# week6helloEcho.net
KiCad netlist of a schematic drawn in EAGLE
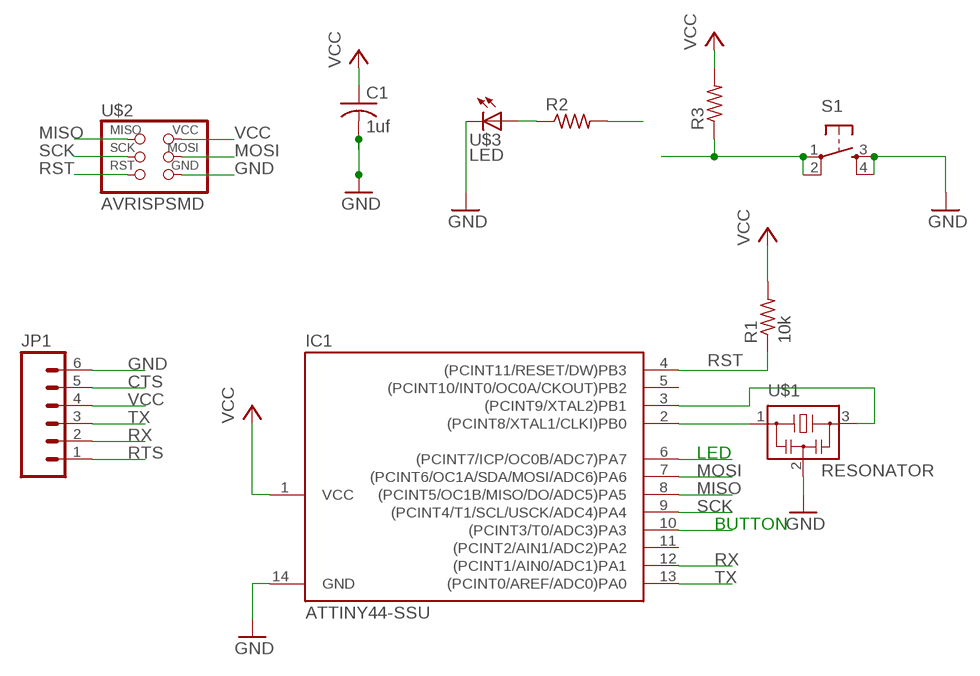
[diagram p0: schematic, sheet 1]

(export (version "E")
  (design (tool "Eeschema 10.0.6"))
  (components
    (comp (ref "C1")
      (value "1uf")
      (footprint "eagle-import:C1206")
      (libsource (lib "eagle-import") (part "C-USC1206"))
    )
    (comp (ref "IC1")
      (value "ATTINY44-SSU")
      (footprint "eagle-import:SOIC14")
      (libsource (lib "eagle-import") (part "ATTINY44-SSU"))
    )
    (comp (ref "JP1")
      (value "M06SMD")
      (footprint "eagle-import:1X06-SMD")
      (libsource (lib "eagle-import") (part "M06SMD"))
    )
    (comp (ref "R1")
      (value "10k")
      (footprint "eagle-import:R1206")
      (libsource (lib "eagle-import") (part "R-US_R1206"))
    )
    (comp (ref "R2")
      (value "RES-US1206")
      (footprint "eagle-import:R1206")
      (libsource (lib "eagle-import") (part "RES-US1206"))
    )
    (comp (ref "R3")
      (value "RES-US1206")
      (footprint "eagle-import:R1206")
      (libsource (lib "eagle-import") (part "RES-US1206"))
    )
    (comp (ref "S1")
      (value "6MM_SWITCH6MM_SWITCH")
      (footprint "eagle-import:6MM_SWITCH")
      (libsource (lib "eagle-import") (part "6MM_SWITCH6MM_SWITCH"))
    )
    (comp (ref "U$1")
      (value "RESONATOR")
      (footprint "eagle-import:EFOBM")
      (libsource (lib "eagle-import") (part "RESONATOR"))
    )
    (comp (ref "U$2")
      (value "AVRISPSMD")
      (footprint "eagle-import:2X03SMD")
      (libsource (lib "eagle-import") (part "AVRISPSMD"))
    )
    (comp (ref "U$3")
      (value "LED")
      (footprint "eagle-import:LED1206")
      (libsource (lib "eagle-import") (part "LED"))
    )
  )
  (nets
    (net (code "1") (name "/BUTTON") (class "Default")
      (node (ref "IC1") (pin "10") (pinfunction "(PCINT3/T0/ADC3)PA3_10") (pintype "bidirectional"))
      (node (ref "R3") (pin "1") (pinfunction "1_1") (pintype "passive"))
      (node (ref "S1") (pin "1") (pinfunction "P_1") (pintype "passive"))
      (node (ref "S1") (pin "2") (pinfunction "P1_2") (pintype "passive"))
    )
    (net (code "2") (name "/CTS") (class "Default")
      (node (ref "JP1") (pin "5") (pinfunction "5_5") (pintype "passive"))
    )
    (net (code "3") (name "/LED") (class "Default")
      (node (ref "IC1") (pin "6") (pinfunction "(PCINT7/ICP/OC0B/ADC7)PA7_6") (pintype "bidirectional"))
      (node (ref "R2") (pin "2") (pinfunction "2_2") (pintype "passive"))
    )
    (net (code "4") (name "/MISO") (class "Default")
      (node (ref "IC1") (pin "8") (pinfunction "(PCINT5/OC1B/MISO/DO/ADC5)PA5_8") (pintype "bidirectional"))
      (node (ref "U$2") (pin "1") (pinfunction "MISO_1") (pintype "passive"))
    )
    (net (code "5") (name "/MOSI") (class "Default")
      (node (ref "IC1") (pin "7") (pinfunction "(PCINT6/OC1A/SDA/MOSI/ADC6)PA6_7") (pintype "bidirectional"))
      (node (ref "U$2") (pin "4") (pinfunction "MOSI_4") (pintype "passive"))
    )
    (net (code "6") (name "/RST") (class "Default")
      (node (ref "IC1") (pin "4") (pinfunction "(PCINT11/RESET/DW)PB3_4") (pintype "bidirectional"))
      (node (ref "R1") (pin "1") (pinfunction "1_1") (pintype "passive"))
      (node (ref "U$2") (pin "5") (pinfunction "RST_5") (pintype "passive"))
    )
    (net (code "7") (name "/RTS") (class "Default")
      (node (ref "JP1") (pin "1") (pinfunction "1_1") (pintype "passive"))
    )
    (net (code "8") (name "/RX") (class "Default")
      (node (ref "IC1") (pin "12") (pinfunction "(PCINT1/AIN0/ADC1)PA1_12") (pintype "bidirectional"))
      (node (ref "JP1") (pin "2") (pinfunction "2_2") (pintype "passive"))
    )
    (net (code "9") (name "/SCK") (class "Default")
      (node (ref "IC1") (pin "9") (pinfunction "(PCINT4/T1/SCL/USCK/ADC4)PA4_9") (pintype "bidirectional"))
      (node (ref "U$2") (pin "3") (pinfunction "SCK_3") (pintype "passive"))
    )
    (net (code "10") (name "/TX") (class "Default")
      (node (ref "IC1") (pin "13") (pinfunction "(PCINT0/AREF/ADC0)PA0_13") (pintype "bidirectional"))
      (node (ref "JP1") (pin "3") (pinfunction "3_3") (pintype "passive"))
    )
    (net (code "11") (name "GND") (class "Default")
      (node (ref "C1") (pin "2") (pinfunction "2_2") (pintype "passive"))
      (node (ref "IC1") (pin "14") (pinfunction "GND_14") (pintype "power_in"))
      (node (ref "JP1") (pin "6") (pinfunction "6_6") (pintype "passive"))
      (node (ref "S1") (pin "3") (pinfunction "S_3") (pintype "passive"))
      (node (ref "S1") (pin "4") (pinfunction "S1_4") (pintype "passive"))
      (node (ref "U$1") (pin "2") (pinfunction "2_2") (pintype "passive"))
      (node (ref "U$2") (pin "6") (pinfunction "GND_6") (pintype "passive"))
      (node (ref "U$3") (pin "2") (pinfunction "C_2") (pintype "passive"))
    )
    (net (code "12") (name "Net-(IC1-(PCINT8{slash}XTAL1{slash}CLKI)PB0)") (class "Default")
      (node (ref "IC1") (pin "2") (pinfunction "(PCINT8/XTAL1/CLKI)PB0_2") (pintype "bidirectional"))
      (node (ref "U$1") (pin "1") (pinfunction "1_1") (pintype "passive"))
    )
    (net (code "13") (name "Net-(IC1-(PCINT9{slash}XTAL2)PB1)") (class "Default")
      (node (ref "IC1") (pin "3") (pinfunction "(PCINT9/XTAL2)PB1_3") (pintype "bidirectional"))
      (node (ref "U$1") (pin "3") (pinfunction "3_3") (pintype "passive"))
    )
    (net (code "14") (name "Net-(U$3-A)") (class "Default")
      (node (ref "R2") (pin "1") (pinfunction "1_1") (pintype "passive"))
      (node (ref "U$3") (pin "1") (pinfunction "A_1") (pintype "passive"))
    )
    (net (code "15") (name "VCC") (class "Default")
      (node (ref "C1") (pin "1") (pinfunction "1_1") (pintype "passive"))
      (node (ref "IC1") (pin "1") (pinfunction "VCC_1") (pintype "power_in"))
      (node (ref "JP1") (pin "4") (pinfunction "4_4") (pintype "passive"))
      (node (ref "R1") (pin "2") (pinfunction "2_2") (pintype "passive"))
      (node (ref "R3") (pin "2") (pinfunction "2_2") (pintype "passive"))
      (node (ref "U$2") (pin "2") (pinfunction "VCC_2") (pintype "passive"))
    )
    (net (code "16") (name "unconnected-(IC1-(PCINT2{slash}AIN1{slash}ADC2)PA2-Pad11)") (class "Default")
      (node (ref "IC1") (pin "11") (pinfunction "(PCINT2/AIN1/ADC2)PA2_11") (pintype "bidirectional"))
    )
    (net (code "17") (name "unconnected-(IC1-(PCINT10{slash}INT0{slash}OC0A{slash}CKOUT)PB2-Pad5)") (class "Default")
      (node (ref "IC1") (pin "5") (pinfunction "(PCINT10/INT0/OC0A/CKOUT)PB2_5") (pintype "bidirectional"))
    )
  )
)
